# Lab7-8_CH3.net
KiCad netlist of a schematic drawn in Altium Designer
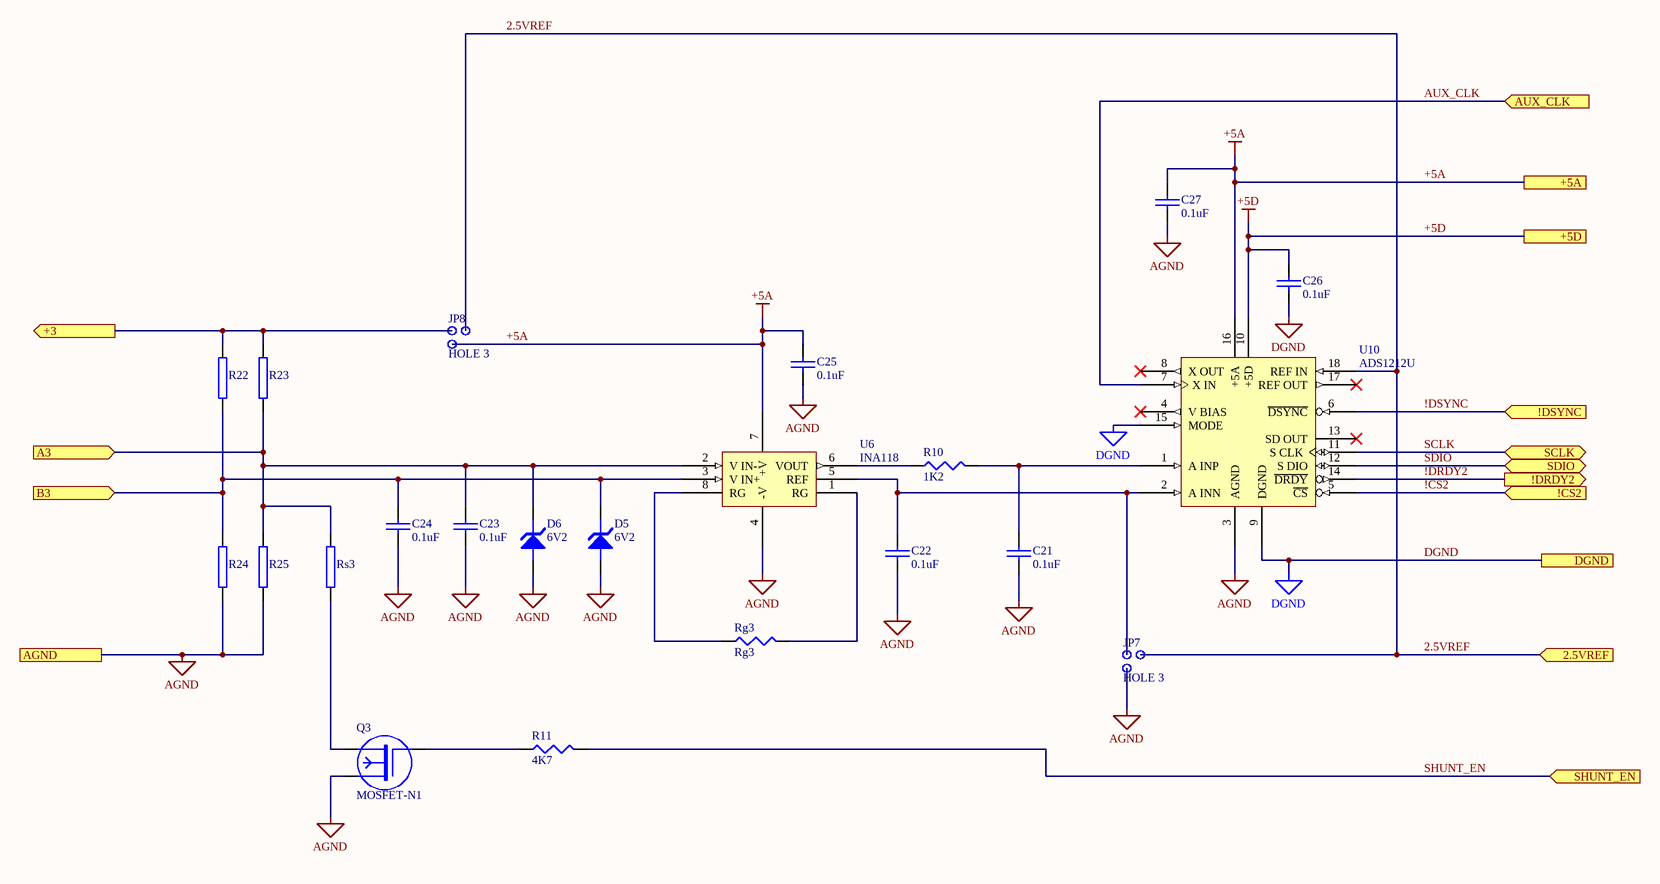
[diagram p0: Lab7-8_CH3.SchDoc]

(export (version "E")
  (design (tool "Eeschema 10.0.6"))
  (components
    (comp (ref "C21")
      (value "0.1uF")
      (footprint "0805")
      (libsource (lib "ECET231_ProjectThree_SCHLIB_Rev02") (part "CAP"))
    )
    (comp (ref "C22")
      (value "0.1uF")
      (footprint "0805")
      (libsource (lib "ECET231_ProjectThree_SCHLIB_Rev02") (part "CAP"))
    )
    (comp (ref "C23")
      (value "0.1uF")
      (footprint "0805")
      (libsource (lib "ECET231_ProjectThree_SCHLIB_Rev02") (part "CAP"))
    )
    (comp (ref "C24")
      (value "0.1uF")
      (footprint "0805")
      (libsource (lib "ECET231_ProjectThree_SCHLIB_Rev02") (part "CAP"))
    )
    (comp (ref "C25")
      (value "0.1uF")
      (footprint "0805")
      (libsource (lib "ECET231_ProjectThree_SCHLIB_Rev02") (part "CAP"))
    )
    (comp (ref "C26")
      (value "0.1uF")
      (footprint "0805")
      (libsource (lib "ECET231_ProjectThree_SCHLIB_Rev02") (part "CAP"))
    )
    (comp (ref "C27")
      (value "0.1uF")
      (footprint "0805")
      (libsource (lib "ECET231_ProjectThree_SCHLIB_Rev02") (part "CAP"))
    )
    (comp (ref "D5")
      (value "6V2")
      (footprint "SOD-123")
      (libsource (lib "ECET231_ProjectThree_SCHLIB_Rev02") (part "ZENER3"))
    )
    (comp (ref "D6")
      (value "6V2")
      (footprint "SOD-123")
      (libsource (lib "ECET231_ProjectThree_SCHLIB_Rev02") (part "ZENER3"))
    )
    (comp (ref "JP7")
      (value "HOLE 3")
      (footprint "RAD0.1A")
      (libsource (lib "ECET231_ProjectThree_SCHLIB_Rev02") (part "HOLE 3"))
    )
    (comp (ref "JP8")
      (value "HOLE 3")
      (footprint "RAD0.1A")
      (libsource (lib "ECET231_ProjectThree_SCHLIB_Rev02") (part "HOLE 3"))
    )
    (comp (ref "Q3")
      (value "MOSFET-N1")
      (footprint "SOT-23")
      (libsource (lib "ECET231_ProjectThree_SCHLIB_Rev02") (part "MOSFET-N1"))
    )
    (comp (ref "R10")
      (value "1K2")
      (footprint "0805")
      (libsource (lib "ECET231_ProjectThree_SCHLIB_Rev02") (part "RES1"))
    )
    (comp (ref "R11")
      (value "4K7")
      (footprint "0805")
      (libsource (lib "ECET231_ProjectThree_SCHLIB_Rev02") (part "RES1"))
    )
    (comp (ref "R22")
      (value "bridge R")
      (footprint "bridge resistor")
      (libsource (lib "ECET231_ProjectThree_SCHLIB_Rev02") (part "RES2"))
    )
    (comp (ref "R23")
      (value "bridge R")
      (footprint "bridge resistor")
      (libsource (lib "ECET231_ProjectThree_SCHLIB_Rev02") (part "RES2"))
    )
    (comp (ref "R24")
      (value "bridge R")
      (footprint "bridge resistor")
      (libsource (lib "ECET231_ProjectThree_SCHLIB_Rev02") (part "RES2"))
    )
    (comp (ref "R25")
      (value "bridge R")
      (footprint "bridge resistor")
      (libsource (lib "ECET231_ProjectThree_SCHLIB_Rev02") (part "RES2"))
    )
    (comp (ref "Rg3")
      (value "Rg3")
      (footprint "0805")
      (libsource (lib "ECET231_ProjectThree_SCHLIB_Rev02") (part "RES1"))
    )
    (comp (ref "Rs3")
      (value "bridge R")
      (footprint "bridge resistor")
      (libsource (lib "ECET231_ProjectThree_SCHLIB_Rev02") (part "RES2"))
    )
    (comp (ref "U6")
      (value "INA118")
      (footprint "SO-8")
      (description "Precision, Low Power Instrumentation Amplifier")
      (libsource (lib "ECET231_ProjectThree_SCHLIB_Rev02") (part "INA118"))
    )
    (comp (ref "U10")
      (value "ADS1212U")
      (footprint "SOIC18")
      (description "22-Bit Analog-to-Digital Converter")
      (libsource (lib "ECET231_ProjectThree_SCHLIB_Rev02") (part "ADS1212U(18)"))
    )
  )
  (nets
    (net (code "1") (name "+5A") (class "Default")
      (node (ref "C25") (pin "1") (pintype "passive"))
      (node (ref "C27") (pin "1") (pintype "passive"))
      (node (ref "JP8") (pin "1") (pinfunction "1_1") (pintype "passive"))
      (node (ref "U10") (pin "16") (pinfunction "+5A_16") (pintype "power_in"))
      (node (ref "U6") (pin "7") (pinfunction "+V_7") (pintype "power_in"))
    )
    (net (code "2") (name "+5D") (class "Default")
      (node (ref "C26") (pin "1") (pintype "passive"))
      (node (ref "U10") (pin "10") (pinfunction "+5D_10") (pintype "power_in"))
    )
    (net (code "3") (name "/!CS2") (class "Default")
      (node (ref "U10") (pin "5") (pinfunction "~{CS}_5") (pintype "input"))
    )
    (net (code "4") (name "/!DRDY2") (class "Default")
      (node (ref "U10") (pin "14") (pinfunction "~{DRDY}_14") (pintype "output"))
    )
    (net (code "5") (name "/!DSYNC") (class "Default")
      (node (ref "U10") (pin "6") (pinfunction "~{DSYNC}_6") (pintype "input"))
    )
    (net (code "6") (name "/+3") (class "Default")
      (node (ref "JP8") (pin "2") (pinfunction "2_2") (pintype "passive"))
      (node (ref "R22") (pin "2") (pintype "passive"))
      (node (ref "R23") (pin "2") (pintype "passive"))
    )
    (net (code "7") (name "/2.5VREF") (class "Default")
      (node (ref "JP7") (pin "3") (pinfunction "3_3") (pintype "passive"))
      (node (ref "JP8") (pin "3") (pinfunction "3_3") (pintype "passive"))
      (node (ref "U10") (pin "18") (pinfunction "REF_IN_18") (pintype "input"))
    )
    (net (code "8") (name "/A3") (class "Default")
      (node (ref "C23") (pin "1") (pintype "passive"))
      (node (ref "D6") (pin "K") (pintype "passive"))
      (node (ref "R23") (pin "1") (pintype "passive"))
      (node (ref "R25") (pin "2") (pintype "passive"))
      (node (ref "Rs3") (pin "2") (pintype "passive"))
      (node (ref "U6") (pin "2") (pinfunction "V_IN-_2") (pintype "input"))
    )
    (net (code "9") (name "/AUX_CLK") (class "Default")
      (node (ref "U10") (pin "7") (pinfunction "X_IN_7") (pintype "input"))
    )
    (net (code "10") (name "/B3") (class "Default")
      (node (ref "C24") (pin "1") (pintype "passive"))
      (node (ref "D5") (pin "K") (pintype "passive"))
      (node (ref "R22") (pin "1") (pintype "passive"))
      (node (ref "R24") (pin "2") (pintype "passive"))
      (node (ref "U6") (pin "3") (pinfunction "V_IN+_3") (pintype "input"))
    )
    (net (code "11") (name "/SCLK") (class "Default")
      (node (ref "U10") (pin "11") (pinfunction "S_CLK_11") (pintype "bidirectional"))
    )
    (net (code "12") (name "/SDIO") (class "Default")
      (node (ref "U10") (pin "12") (pinfunction "S_DIO_12") (pintype "bidirectional"))
    )
    (net (code "13") (name "/SHUNT_EN") (class "Default") (node (ref "R11") (pin "2") (pintype "passive")))
    (net (code "14") (name "AGND") (class "Default")
      (node (ref "C21") (pin "2") (pintype "passive"))
      (node (ref "C22") (pin "2") (pintype "passive"))
      (node (ref "C23") (pin "2") (pintype "passive"))
      (node (ref "C24") (pin "2") (pintype "passive"))
      (node (ref "C25") (pin "2") (pintype "passive"))
      (node (ref "C27") (pin "2") (pintype "passive"))
      (node (ref "D5") (pin "A") (pintype "passive"))
      (node (ref "D6") (pin "A") (pintype "passive"))
      (node (ref "JP7") (pin "1") (pinfunction "1_1") (pintype "passive"))
      (node (ref "Q3") (pin "2") (pintype "passive"))
      (node (ref "R24") (pin "1") (pintype "passive"))
      (node (ref "R25") (pin "1") (pintype "passive"))
      (node (ref "U10") (pin "3") (pinfunction "AGND_3") (pintype "power_in"))
      (node (ref "U6") (pin "4") (pinfunction "-V_4") (pintype "power_in"))
    )
    (net (code "15") (name "DGND") (class "Default")
      (node (ref "C26") (pin "2") (pintype "passive"))
      (node (ref "U10") (pin "15") (pinfunction "MODE_15") (pintype "input"))
      (node (ref "U10") (pin "9") (pinfunction "DGND_9") (pintype "power_in"))
    )
    (net (code "16") (name "Net-(Q3-Pad1)") (class "Default")
      (node (ref "Q3") (pin "1") (pintype "passive"))
      (node (ref "R11") (pin "1") (pintype "passive"))
    )
    (net (code "17") (name "Net-(Q3-Pad3)") (class "Default")
      (node (ref "Q3") (pin "3") (pintype "passive"))
      (node (ref "Rs3") (pin "1") (pintype "passive"))
    )
    (net (code "18") (name "Net-(Rg3-Pad1)") (class "Default")
      (node (ref "Rg3") (pin "1") (pintype "passive"))
      (node (ref "U6") (pin "8") (pinfunction "RG_8") (pintype "passive"))
    )
    (net (code "19") (name "Net-(Rg3-Pad2)") (class "Default")
      (node (ref "Rg3") (pin "2") (pintype "passive"))
      (node (ref "U6") (pin "1") (pinfunction "RG_1") (pintype "passive"))
    )
    (net (code "20") (name "Net-(U6-VOUT)") (class "Default")
      (node (ref "R10") (pin "1") (pintype "passive"))
      (node (ref "U6") (pin "6") (pinfunction "VOUT_6") (pintype "output"))
    )
    (net (code "21") (name "Net-(U10-A_INN)") (class "Default")
      (node (ref "C22") (pin "1") (pintype "passive"))
      (node (ref "JP7") (pin "2") (pinfunction "2_2") (pintype "passive"))
      (node (ref "U10") (pin "2") (pinfunction "A_INN_2") (pintype "input"))
      (node (ref "U6") (pin "5") (pinfunction "REF_5") (pintype "passive"))
    )
    (net (code "22") (name "Net-(U10-A_INP)") (class "Default")
      (node (ref "C21") (pin "1") (pintype "passive"))
      (node (ref "R10") (pin "2") (pintype "passive"))
      (node (ref "U10") (pin "1") (pinfunction "A_INP_1") (pintype "input"))
    )
    (net (code "23") (name "unconnected-(U10-REF_OUT-Pad17)") (class "Default")
      (node (ref "U10") (pin "17") (pinfunction "REF_OUT_17") (pintype "output+no_connect"))
    )
    (net (code "24") (name "unconnected-(U10-SD_OUT-Pad13)") (class "Default")
      (node (ref "U10") (pin "13") (pinfunction "SD_OUT_13") (pintype "tri_state+no_connect"))
    )
    (net (code "25") (name "unconnected-(U10-V_BIAS-Pad4)") (class "Default")
      (node (ref "U10") (pin "4") (pinfunction "V_BIAS_4") (pintype "output+no_connect"))
    )
    (net (code "26") (name "unconnected-(U10-X_OUT-Pad8)") (class "Default")
      (node (ref "U10") (pin "8") (pinfunction "X_OUT_8") (pintype "output+no_connect"))
    )
  )
)
